# Board1_v1.net
KiCad netlist of a schematic drawn in Altium Designer
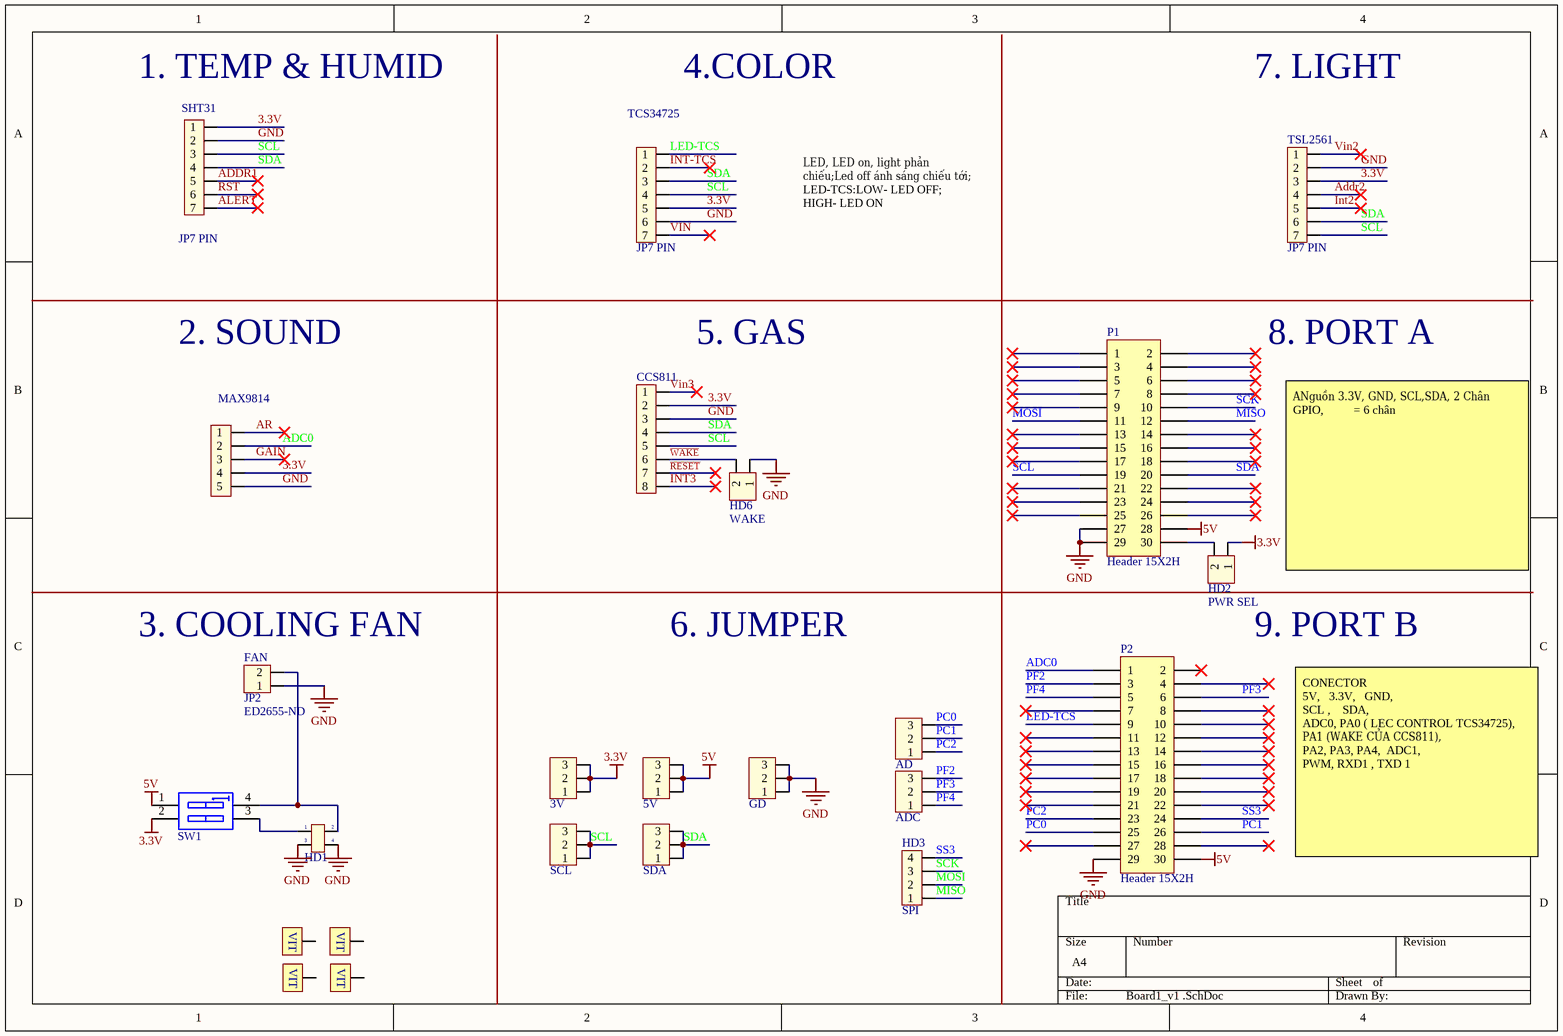
[diagram p0: Board1_v1 .SchDoc]

(export (version "E")
  (design (tool "Eeschema 10.0.6"))
  (components
    (comp (ref "3V") (value "Header 3") (footprint "Header_3") (libsource (lib "lpson") (part "Header3")))
    (comp (ref "5V") (value "Header 3") (footprint "Header_3") (libsource (lib "lpson") (part "Header3")))
    (comp (ref "AD") (value "Header 3") (footprint "Header_3") (libsource (lib "lpson") (part "Header3")))
    (comp (ref "ADC") (value "Header 3") (footprint "Header_3") (libsource (lib "lpson") (part "Header3")))
    (comp (ref "CCS811")
      (value "JP8 PIN")
      (footprint "CCS811")
      (libsource (lib "quangnguyen_lib_altium") (part "JP8"))
    )
    (comp (ref "FAN")
      (value "JP2")
      (footprint "CON2")
      (description "Terminal 2pin 5mm")
      (fields
        (field (name "MANUFACTURER") "On Shore Technology Inc.")
        (field (name "MANUFACTURER PART NUMBER") "OSTTH020160")
        (field (name "SUPPLIER PART NUMBER 1") "ED2655-ND")
      )
      (libsource (lib "lpson") (part "Terminal 2"))
    )
    (comp (ref "GD") (value "Header 3") (footprint "Header_3") (libsource (lib "lpson") (part "Header3")))
    (comp (ref "HD1") (value "Jumper 2x2") (footprint "HDR2X2") (libsource (lib "lpson") (part "JP2x2")))
    (comp (ref "HD2")
      (value "PWR SEL")
      (footprint "Header_2")
      (description "Header 2")
      (libsource (lib "lpson") (part "Header2"))
    )
    (comp (ref "HD3")
      (value "SPI")
      (footprint "Header_4")
      (description "Header 4")
      (libsource (lib "lpson") (part "Header4"))
    )
    (comp (ref "HD6")
      (value "WAKE")
      (footprint "Header_2")
      (description "Header 2")
      (libsource (lib "lpson") (part "Header2"))
    )
    (comp (ref "MAX9814")
      (value "JP5")
      (footprint "MAX9814")
      (libsource (lib "quangnguyen_lib_altium") (part "JP5"))
    )
    (comp (ref "P1")
      (value "Header 15X2H")
      (footprint "HED15X2H")
      (description "Header, 15-Pin, Dual row, Right Angle")
      (fields (field (name "PUBLISHER") "Altium Limited"))
      (libsource (lib "My Library") (part "Header 15X2H"))
    )
    (comp (ref "P2")
      (value "Header 15X2H")
      (footprint "HED15X2H")
      (description "Header, 15-Pin, Dual row, Right Angle")
      (fields (field (name "PUBLISHER") "Altium Limited"))
      (libsource (lib "My Library") (part "Header 15X2H"))
    )
    (comp (ref "SCL") (value "Header 3") (footprint "Header_3") (libsource (lib "lpson") (part "Header3")))
    (comp (ref "SDA") (value "Header 3") (footprint "Header_3") (libsource (lib "lpson") (part "Header3")))
    (comp (ref "SHT31")
      (value "JP7 PIN")
      (footprint "SHT31")
      (libsource (lib "quangnguyen_lib_altium") (part "JP7"))
    )
    (comp (ref "SW1")
      (value "SW - DIP2")
      (footprint "DIP_Switch2")
      (description "DIP Switch, 2 Position, SPST")
      (libsource (lib "lpson") (part "SWDIP-2"))
    )
    (comp (ref "TCS34725")
      (value "JP7 PIN")
      (footprint "TCS34725")
      (libsource (lib "quangnguyen_lib_altium") (part "JP7"))
    )
    (comp (ref "TSL2561")
      (value "JP7 PIN")
      (footprint "TSL2561")
      (libsource (lib "quangnguyen_lib_altium") (part "JP7"))
    )
    (comp (ref "VIT2")
      (value "1")
      (footprint "Screw 3 small")
      (description "Oc Vit")
      (libsource (lib "quangnguyen_lib_altium") (part "VIT"))
    )
    (comp (ref "VIT3")
      (value "1")
      (footprint "Screw 3 small")
      (description "Oc Vit")
      (libsource (lib "quangnguyen_lib_altium") (part "VIT"))
    )
    (comp (ref "VIT5")
      (value "1")
      (footprint "Screw 3 small")
      (description "Oc Vit")
      (libsource (lib "quangnguyen_lib_altium") (part "VIT"))
    )
    (comp (ref "VIT6")
      (value "1")
      (footprint "Screw 3 small")
      (description "Oc Vit")
      (libsource (lib "quangnguyen_lib_altium") (part "VIT"))
    )
  )
  (nets
    (net (code "1") (name "/ADC0") (class "Default")
      (node (ref "MAX9814") (pin "2") (pinfunction "2_2") (pintype "passive"))
      (node (ref "P2") (pin "1") (pinfunction "1_1") (pintype "passive"))
    )
    (net (code "2") (name "/ADDR1") (class "Default")
      (node (ref "SHT31") (pin "5") (pinfunction "5_5") (pintype "passive+no_connect"))
    )
    (net (code "3") (name "/ALERT") (class "Default")
      (node (ref "SHT31") (pin "7") (pinfunction "7_7") (pintype "passive+no_connect"))
    )
    (net (code "4") (name "/AR") (class "Default")
      (node (ref "MAX9814") (pin "1") (pinfunction "1_1") (pintype "passive+no_connect"))
    )
    (net (code "5") (name "/Addr2") (class "Default")
      (node (ref "TSL2561") (pin "4") (pinfunction "4_4") (pintype "passive+no_connect"))
    )
    (net (code "6") (name "/GAIN") (class "Default")
      (node (ref "MAX9814") (pin "3") (pinfunction "3_3") (pintype "passive+no_connect"))
    )
    (net (code "7") (name "/INT-TCS") (class "Default")
      (node (ref "TCS34725") (pin "2") (pinfunction "2_2") (pintype "passive+no_connect"))
    )
    (net (code "8") (name "/INT3") (class "Default")
      (node (ref "CCS811") (pin "8") (pinfunction "8_8") (pintype "passive+no_connect"))
    )
    (net (code "9") (name "/Int2") (class "Default")
      (node (ref "TSL2561") (pin "5") (pinfunction "5_5") (pintype "passive+no_connect"))
    )
    (net (code "10") (name "/LED-TCS") (class "Default")
      (node (ref "P2") (pin "9") (pinfunction "9_9") (pintype "passive"))
      (node (ref "TCS34725") (pin "1") (pinfunction "1_1") (pintype "passive"))
    )
    (net (code "11") (name "/MISO") (class "Default")
      (node (ref "HD3") (pin "1") (pinfunction "1_1") (pintype "passive"))
      (node (ref "P1") (pin "12") (pinfunction "12_12") (pintype "passive"))
    )
    (net (code "12") (name "/MOSI") (class "Default")
      (node (ref "HD3") (pin "2") (pinfunction "2_2") (pintype "passive"))
      (node (ref "P1") (pin "11") (pinfunction "11_11") (pintype "passive"))
    )
    (net (code "13") (name "/PC0") (class "Default")
      (node (ref "AD") (pin "3") (pinfunction "3_3") (pintype "passive"))
      (node (ref "P2") (pin "25") (pinfunction "25_25") (pintype "passive"))
    )
    (net (code "14") (name "/PC1") (class "Default")
      (node (ref "AD") (pin "2") (pinfunction "2_2") (pintype "passive"))
      (node (ref "P2") (pin "26") (pinfunction "26_26") (pintype "passive"))
    )
    (net (code "15") (name "/PC2") (class "Default")
      (node (ref "AD") (pin "1") (pinfunction "1_1") (pintype "passive"))
      (node (ref "P2") (pin "23") (pinfunction "23_23") (pintype "passive"))
    )
    (net (code "16") (name "/PF2") (class "Default")
      (node (ref "ADC") (pin "3") (pinfunction "3_3") (pintype "passive"))
      (node (ref "P2") (pin "3") (pinfunction "3_3") (pintype "passive"))
    )
    (net (code "17") (name "/PF3") (class "Default")
      (node (ref "ADC") (pin "2") (pinfunction "2_2") (pintype "passive"))
      (node (ref "P2") (pin "6") (pinfunction "6_6") (pintype "passive"))
    )
    (net (code "18") (name "/PF4") (class "Default")
      (node (ref "ADC") (pin "1") (pinfunction "1_1") (pintype "passive"))
      (node (ref "P2") (pin "5") (pinfunction "5_5") (pintype "passive"))
    )
    (net (code "19") (name "/RST") (class "Default")
      (node (ref "SHT31") (pin "6") (pinfunction "6_6") (pintype "passive+no_connect"))
    )
    (net (code "20") (name "/SCK") (class "Default")
      (node (ref "HD3") (pin "3") (pinfunction "3_3") (pintype "passive"))
      (node (ref "P1") (pin "10") (pinfunction "10_10") (pintype "passive"))
    )
    (net (code "21") (name "/SCL") (class "Default")
      (node (ref "CCS811") (pin "5") (pinfunction "5_5") (pintype "passive"))
      (node (ref "P1") (pin "19") (pinfunction "19_19") (pintype "passive"))
      (node (ref "SCL") (pin "1") (pinfunction "1_1") (pintype "passive"))
      (node (ref "SCL") (pin "2") (pinfunction "2_2") (pintype "passive"))
      (node (ref "SCL") (pin "3") (pinfunction "3_3") (pintype "passive"))
      (node (ref "SHT31") (pin "3") (pinfunction "3_3") (pintype "passive"))
      (node (ref "TCS34725") (pin "4") (pinfunction "4_4") (pintype "passive"))
      (node (ref "TSL2561") (pin "7") (pinfunction "7_7") (pintype "passive"))
    )
    (net (code "22") (name "/SDA") (class "Default")
      (node (ref "CCS811") (pin "4") (pinfunction "4_4") (pintype "passive"))
      (node (ref "P1") (pin "20") (pinfunction "20_20") (pintype "passive"))
      (node (ref "SDA") (pin "1") (pinfunction "1_1") (pintype "passive"))
      (node (ref "SDA") (pin "2") (pinfunction "2_2") (pintype "passive"))
      (node (ref "SDA") (pin "3") (pinfunction "3_3") (pintype "passive"))
      (node (ref "SHT31") (pin "4") (pinfunction "4_4") (pintype "passive"))
      (node (ref "TCS34725") (pin "3") (pinfunction "3_3") (pintype "passive"))
      (node (ref "TSL2561") (pin "6") (pinfunction "6_6") (pintype "passive"))
    )
    (net (code "23") (name "/SS3") (class "Default")
      (node (ref "HD3") (pin "4") (pinfunction "4_4") (pintype "passive"))
      (node (ref "P2") (pin "24") (pinfunction "24_24") (pintype "passive"))
    )
    (net (code "24") (name "/VIN") (class "Default")
      (node (ref "TCS34725") (pin "7") (pinfunction "7_7") (pintype "passive+no_connect"))
    )
    (net (code "25") (name "/Vin2") (class "Default")
      (node (ref "TSL2561") (pin "1") (pinfunction "1_1") (pintype "passive+no_connect"))
    )
    (net (code "26") (name "/Vin3") (class "Default")
      (node (ref "CCS811") (pin "1") (pinfunction "1_1") (pintype "passive+no_connect"))
    )
    (net (code "27") (name "/~{RESET}") (class "Default")
      (node (ref "CCS811") (pin "7") (pinfunction "7_7") (pintype "passive+no_connect"))
    )
    (net (code "28") (name "/~{WAKE}") (class "Default")
      (node (ref "CCS811") (pin "6") (pinfunction "6_6") (pintype "passive"))
      (node (ref "HD6") (pin "2") (pinfunction "2_2") (pintype "passive"))
    )
    (net (code "29") (name "3.3V") (class "Default")
      (node (ref "3V") (pin "1") (pinfunction "1_1") (pintype "passive"))
      (node (ref "3V") (pin "2") (pinfunction "2_2") (pintype "passive"))
      (node (ref "3V") (pin "3") (pinfunction "3_3") (pintype "passive"))
      (node (ref "CCS811") (pin "2") (pinfunction "2_2") (pintype "passive"))
      (node (ref "HD2") (pin "1") (pinfunction "1_1") (pintype "passive"))
      (node (ref "MAX9814") (pin "4") (pinfunction "4_4") (pintype "passive"))
      (node (ref "SHT31") (pin "1") (pinfunction "1_1") (pintype "passive"))
      (node (ref "SW1") (pin "2") (pinfunction "A2_2") (pintype "passive"))
      (node (ref "TCS34725") (pin "5") (pinfunction "5_5") (pintype "passive"))
      (node (ref "TSL2561") (pin "3") (pinfunction "3_3") (pintype "passive"))
    )
    (net (code "30") (name "5V") (class "Default")
      (node (ref "5V") (pin "1") (pinfunction "1_1") (pintype "passive"))
      (node (ref "5V") (pin "2") (pinfunction "2_2") (pintype "passive"))
      (node (ref "5V") (pin "3") (pinfunction "3_3") (pintype "passive"))
      (node (ref "P1") (pin "28") (pinfunction "28_28") (pintype "passive"))
      (node (ref "P2") (pin "30") (pinfunction "30_30") (pintype "passive"))
      (node (ref "SW1") (pin "1") (pinfunction "A1_1") (pintype "passive"))
    )
    (net (code "31") (name "GND") (class "Default")
      (node (ref "CCS811") (pin "3") (pinfunction "3_3") (pintype "passive"))
      (node (ref "FAN") (pin "1") (pinfunction "1_1") (pintype "passive"))
      (node (ref "GD") (pin "1") (pinfunction "1_1") (pintype "passive"))
      (node (ref "GD") (pin "2") (pinfunction "2_2") (pintype "passive"))
      (node (ref "GD") (pin "3") (pinfunction "3_3") (pintype "passive"))
      (node (ref "HD1") (pin "3") (pinfunction "3_3") (pintype "passive"))
      (node (ref "HD1") (pin "4") (pinfunction "4_4") (pintype "passive"))
      (node (ref "HD6") (pin "1") (pinfunction "1_1") (pintype "passive"))
      (node (ref "MAX9814") (pin "5") (pinfunction "5_5") (pintype "passive"))
      (node (ref "P1") (pin "27") (pinfunction "27_27") (pintype "passive"))
      (node (ref "P1") (pin "29") (pinfunction "29_29") (pintype "passive"))
      (node (ref "P2") (pin "29") (pinfunction "29_29") (pintype "passive"))
      (node (ref "SHT31") (pin "2") (pinfunction "2_2") (pintype "passive"))
      (node (ref "TCS34725") (pin "6") (pinfunction "6_6") (pintype "passive"))
      (node (ref "TSL2561") (pin "2") (pinfunction "2_2") (pintype "passive"))
    )
    (net (code "32") (name "Net-(HD2-Pad2)") (class "Default")
      (node (ref "HD2") (pin "2") (pinfunction "2_2") (pintype "passive"))
      (node (ref "P1") (pin "30") (pinfunction "30_30") (pintype "passive"))
    )
    (net (code "33") (name "Net-(SW1-A3)") (class "Default")
      (node (ref "HD1") (pin "1") (pinfunction "1_1") (pintype "passive"))
      (node (ref "SW1") (pin "3") (pinfunction "A3_3") (pintype "passive"))
    )
    (net (code "34") (name "Net-(SW1-A4)") (class "Default")
      (node (ref "FAN") (pin "2") (pinfunction "2_2") (pintype "passive"))
      (node (ref "HD1") (pin "2") (pinfunction "2_2") (pintype "passive"))
      (node (ref "SW1") (pin "4") (pinfunction "A4_4") (pintype "passive"))
    )
    (net (code "35") (name "unconnected-(P1-Pad1)") (class "Default")
      (node (ref "P1") (pin "1") (pinfunction "1_1") (pintype "passive+no_connect"))
    )
    (net (code "36") (name "unconnected-(P1-Pad2)") (class "Default")
      (node (ref "P1") (pin "2") (pinfunction "2_2") (pintype "passive+no_connect"))
    )
    (net (code "37") (name "unconnected-(P1-Pad3)") (class "Default")
      (node (ref "P1") (pin "3") (pinfunction "3_3") (pintype "passive+no_connect"))
    )
    (net (code "38") (name "unconnected-(P1-Pad4)") (class "Default")
      (node (ref "P1") (pin "4") (pinfunction "4_4") (pintype "passive+no_connect"))
    )
    (net (code "39") (name "unconnected-(P1-Pad5)") (class "Default")
      (node (ref "P1") (pin "5") (pinfunction "5_5") (pintype "passive+no_connect"))
    )
    (net (code "40") (name "unconnected-(P1-Pad6)") (class "Default")
      (node (ref "P1") (pin "6") (pinfunction "6_6") (pintype "passive+no_connect"))
    )
    (net (code "41") (name "unconnected-(P1-Pad7)") (class "Default")
      (node (ref "P1") (pin "7") (pinfunction "7_7") (pintype "passive+no_connect"))
    )
    (net (code "42") (name "unconnected-(P1-Pad8)") (class "Default")
      (node (ref "P1") (pin "8") (pinfunction "8_8") (pintype "passive+no_connect"))
    )
    (net (code "43") (name "unconnected-(P1-Pad9)") (class "Default")
      (node (ref "P1") (pin "9") (pinfunction "9_9") (pintype "passive+no_connect"))
    )
    (net (code "44") (name "unconnected-(P1-Pad13)") (class "Default")
      (node (ref "P1") (pin "13") (pinfunction "13_13") (pintype "passive+no_connect"))
    )
    (net (code "45") (name "unconnected-(P1-Pad14)") (class "Default")
      (node (ref "P1") (pin "14") (pinfunction "14_14") (pintype "passive+no_connect"))
    )
    (net (code "46") (name "unconnected-(P1-Pad15)") (class "Default")
      (node (ref "P1") (pin "15") (pinfunction "15_15") (pintype "passive+no_connect"))
    )
    (net (code "47") (name "unconnected-(P1-Pad16)") (class "Default")
      (node (ref "P1") (pin "16") (pinfunction "16_16") (pintype "passive+no_connect"))
    )
    (net (code "48") (name "unconnected-(P1-Pad17)") (class "Default")
      (node (ref "P1") (pin "17") (pinfunction "17_17") (pintype "passive+no_connect"))
    )
    (net (code "49") (name "unconnected-(P1-Pad18)") (class "Default")
      (node (ref "P1") (pin "18") (pinfunction "18_18") (pintype "passive+no_connect"))
    )
    (net (code "50") (name "unconnected-(P1-Pad21)") (class "Default")
      (node (ref "P1") (pin "21") (pinfunction "21_21") (pintype "passive+no_connect"))
    )
    (net (code "51") (name "unconnected-(P1-Pad22)") (class "Default")
      (node (ref "P1") (pin "22") (pinfunction "22_22") (pintype "passive+no_connect"))
    )
    (net (code "52") (name "unconnected-(P1-Pad23)") (class "Default")
      (node (ref "P1") (pin "23") (pinfunction "23_23") (pintype "passive+no_connect"))
    )
    (net (code "53") (name "unconnected-(P1-Pad24)") (class "Default")
      (node (ref "P1") (pin "24") (pinfunction "24_24") (pintype "passive+no_connect"))
    )
    (net (code "54") (name "unconnected-(P1-Pad25)") (class "Default")
      (node (ref "P1") (pin "25") (pinfunction "25_25") (pintype "passive+no_connect"))
    )
    (net (code "55") (name "unconnected-(P1-Pad26)") (class "Default")
      (node (ref "P1") (pin "26") (pinfunction "26_26") (pintype "passive+no_connect"))
    )
    (net (code "56") (name "unconnected-(P2-Pad2)") (class "Default")
      (node (ref "P2") (pin "2") (pinfunction "2_2") (pintype "passive+no_connect"))
    )
    (net (code "57") (name "unconnected-(P2-Pad4)") (class "Default")
      (node (ref "P2") (pin "4") (pinfunction "4_4") (pintype "passive+no_connect"))
    )
    (net (code "58") (name "unconnected-(P2-Pad7)") (class "Default")
      (node (ref "P2") (pin "7") (pinfunction "7_7") (pintype "passive+no_connect"))
    )
    (net (code "59") (name "unconnected-(P2-Pad8)") (class "Default")
      (node (ref "P2") (pin "8") (pinfunction "8_8") (pintype "passive+no_connect"))
    )
    (net (code "60") (name "unconnected-(P2-Pad10)") (class "Default")
      (node (ref "P2") (pin "10") (pinfunction "10_10") (pintype "passive+no_connect"))
    )
    (net (code "61") (name "unconnected-(P2-Pad11)") (class "Default")
      (node (ref "P2") (pin "11") (pinfunction "11_11") (pintype "passive+no_connect"))
    )
    (net (code "62") (name "unconnected-(P2-Pad12)") (class "Default")
      (node (ref "P2") (pin "12") (pinfunction "12_12") (pintype "passive+no_connect"))
    )
    (net (code "63") (name "unconnected-(P2-Pad13)") (class "Default")
      (node (ref "P2") (pin "13") (pinfunction "13_13") (pintype "passive+no_connect"))
    )
    (net (code "64") (name "unconnected-(P2-Pad14)") (class "Default")
      (node (ref "P2") (pin "14") (pinfunction "14_14") (pintype "passive+no_connect"))
    )
    (net (code "65") (name "unconnected-(P2-Pad15)") (class "Default")
      (node (ref "P2") (pin "15") (pinfunction "15_15") (pintype "passive+no_connect"))
    )
    (net (code "66") (name "unconnected-(P2-Pad16)") (class "Default")
      (node (ref "P2") (pin "16") (pinfunction "16_16") (pintype "passive+no_connect"))
    )
    (net (code "67") (name "unconnected-(P2-Pad17)") (class "Default")
      (node (ref "P2") (pin "17") (pinfunction "17_17") (pintype "passive+no_connect"))
    )
    (net (code "68") (name "unconnected-(P2-Pad18)") (class "Default")
      (node (ref "P2") (pin "18") (pinfunction "18_18") (pintype "passive+no_connect"))
    )
    (net (code "69") (name "unconnected-(P2-Pad19)") (class "Default")
      (node (ref "P2") (pin "19") (pinfunction "19_19") (pintype "passive+no_connect"))
    )
    (net (code "70") (name "unconnected-(P2-Pad20)") (class "Default")
      (node (ref "P2") (pin "20") (pinfunction "20_20") (pintype "passive+no_connect"))
    )
    (net (code "71") (name "unconnected-(P2-Pad21)") (class "Default")
      (node (ref "P2") (pin "21") (pinfunction "21_21") (pintype "passive+no_connect"))
    )
    (net (code "72") (name "unconnected-(P2-Pad22)") (class "Default")
      (node (ref "P2") (pin "22") (pinfunction "22_22") (pintype "passive+no_connect"))
    )
    (net (code "73") (name "unconnected-(P2-Pad27)") (class "Default")
      (node (ref "P2") (pin "27") (pinfunction "27_27") (pintype "passive+no_connect"))
    )
    (net (code "74") (name "unconnected-(P2-Pad28)") (class "Default")
      (node (ref "P2") (pin "28") (pinfunction "28_28") (pintype "passive+no_connect"))
    )
    (net (code "75") (name "unconnected-(VIT2-1-PadVIT1)") (class "Default")
      (node (ref "VIT2") (pin "VIT1") (pinfunction "1_VIT1") (pintype "passive"))
    )
    (net (code "76") (name "unconnected-(VIT3-1-PadVIT1)") (class "Default")
      (node (ref "VIT3") (pin "VIT1") (pinfunction "1_VIT1") (pintype "passive"))
    )
    (net (code "77") (name "unconnected-(VIT5-1-PadVIT1)") (class "Default")
      (node (ref "VIT5") (pin "VIT1") (pinfunction "1_VIT1") (pintype "passive"))
    )
    (net (code "78") (name "unconnected-(VIT6-1-PadVIT1)") (class "Default")
      (node (ref "VIT6") (pin "VIT1") (pinfunction "1_VIT1") (pintype "passive"))
    )
  )
)
